# 3_3V_Converter.net
KiCad netlist of a schematic drawn in Altium Designer
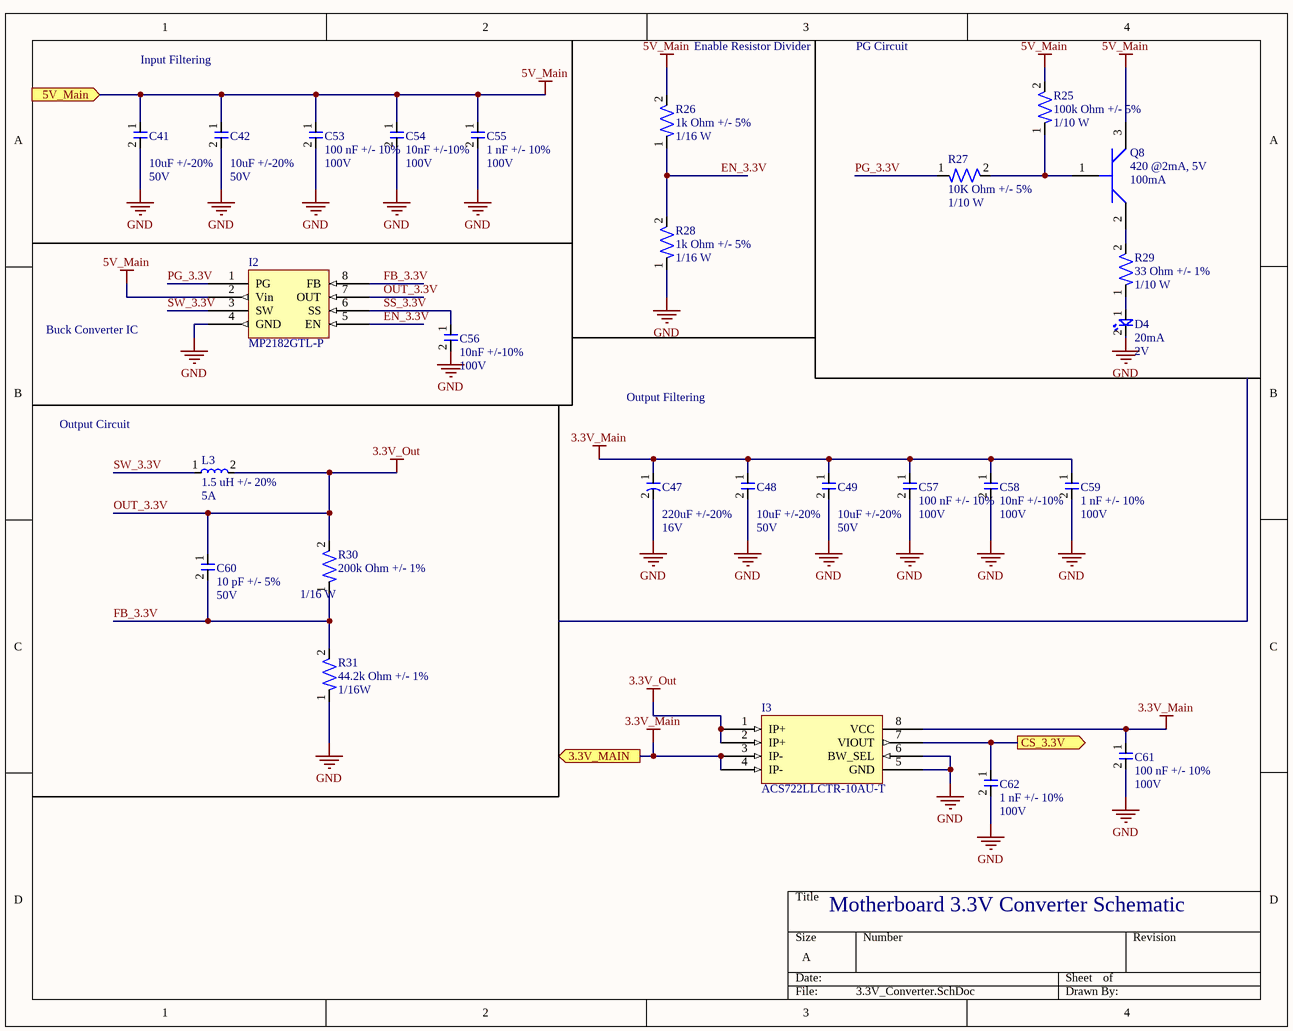
[diagram p0: 3.3V_Converter.SchDoc]

(export (version "E")
  (design (tool "Eeschema 10.0.6"))
  (components
    (comp (ref "C41")
      (value "CL31B106KBHNNNE")
      (footprint "CAP-1206")
      (description "10 µF ±10% 50V Ceramic Capacitor X7R 1206 (3216 Metric)")
      (fields
        (field (name "MANUFACTURER") "Samsung Electro-Mechanics")
        (field (name "CAPACITANCE") "10uF +/-20%")
        (field (name "VOLTAGE RATING") "50V")
      )
      (libsource (lib "MasterLib") (part "CAP-10U-0001"))
    )
    (comp (ref "C42")
      (value "CL31B106KBHNNNE")
      (footprint "CAP-1206")
      (description "10 µF ±10% 50V Ceramic Capacitor X7R 1206 (3216 Metric)")
      (fields
        (field (name "MANUFACTURER") "Samsung Electro-Mechanics")
        (field (name "CAPACITANCE") "10uF +/-20%")
        (field (name "VOLTAGE RATING") "50V")
      )
      (libsource (lib "MasterLib") (part "CAP-10U-0001"))
    )
    (comp (ref "C47")
      (value "UUD1C221MCL1GS")
      (footprint "ELEC-220U-0001")
      (description "220 µF 16 V Aluminum Electrolytic Capacitors Radial, Can - SMD 2000 Hrs @ 105°C")
      (fields
        (field (name "MANUFACTURER") "Nichicon")
        (field (name "CAPACITANCE") "220uF +/-20%")
        (field (name "VOLTAGE RATING") "16V")
      )
      (libsource (lib "MasterLib") (part "ELEC-220U-0001"))
    )
    (comp (ref "C48")
      (value "CL31B106KBHNNNE")
      (footprint "CAP-1206")
      (description "10 µF ±10% 50V Ceramic Capacitor X7R 1206 (3216 Metric)")
      (fields
        (field (name "MANUFACTURER") "Samsung Electro-Mechanics")
        (field (name "CAPACITANCE") "10uF +/-20%")
        (field (name "VOLTAGE RATING") "50V")
      )
      (libsource (lib "MasterLib") (part "CAP-10U-0001"))
    )
    (comp (ref "C49")
      (value "CL31B106KBHNNNE")
      (footprint "CAP-1206")
      (description "10 µF ±10% 50V Ceramic Capacitor X7R 1206 (3216 Metric)")
      (fields
        (field (name "MANUFACTURER") "Samsung Electro-Mechanics")
        (field (name "CAPACITANCE") "10uF +/-20%")
        (field (name "VOLTAGE RATING") "50V")
      )
      (libsource (lib "MasterLib") (part "CAP-10U-0001"))
    )
    (comp (ref "C53")
      (value "CC0603KRX7R0BB104")
      (footprint "CAP-0603")
      (description "100V 100nF X7R ±10% 0603 Multilayer Ceramic Capacitors MLCC - SMD/SMT ROHS")
      (fields
        (field (name "JLC PART NUMBER") "C113803")
        (field (name "CAPACITANCE") "100 nF +/- 10%")
        (field (name "VOLTAGE") "100V")
      )
      (libsource (lib "MasterLib") (part "CAP-100N-0002-JLC"))
    )
    (comp (ref "C54")
      (value "CC0603KRX7R0BB103")
      (footprint "CAP-0603")
      (description "100V 10nF X7R ±10% 0603 Multilayer Ceramic Capacitors MLCC - SMD/SMT ROHS")
      (fields
        (field (name "MANUFACTURER") "Yageo")
        (field (name "JLC PART NUMBER") "C107059")
        (field (name "CAPACITANCE") "10nF +/-10%")
        (field (name "VOLTAGE RATING") "100V")
      )
      (libsource (lib "MasterLib") (part "CAP-10N-0003-JLC"))
    )
    (comp (ref "C55")
      (value "C0402C102K1GECAUTO")
      (footprint "CAP-0402")
      (description "100V 1nF C0G ±10% 0402 Multilayer Ceramic Capacitors MLCC - SMD/SMT ROHS")
      (fields
        (field (name "CAPACITANCE") "1 nF +/- 10%")
        (field (name "VOLTAGE") "100V")
        (field (name "JLC PART NUMBER") "C696348")
      )
      (libsource (lib "MasterLib") (part "CAP-1N-0004-JLC"))
    )
    (comp (ref "C56")
      (value "CC0603KRX7R0BB103")
      (footprint "CAP-0603")
      (description "100V 10nF X7R ±10% 0603 Multilayer Ceramic Capacitors MLCC - SMD/SMT ROHS")
      (fields
        (field (name "MANUFACTURER") "Yageo")
        (field (name "JLC PART NUMBER") "C107059")
        (field (name "CAPACITANCE") "10nF +/-10%")
        (field (name "VOLTAGE RATING") "100V")
      )
      (libsource (lib "MasterLib") (part "CAP-10N-0003-JLC"))
    )
    (comp (ref "C57")
      (value "CC0603KRX7R0BB104")
      (footprint "CAP-0603")
      (description "100V 100nF X7R ±10% 0603 Multilayer Ceramic Capacitors MLCC - SMD/SMT ROHS")
      (fields
        (field (name "JLC PART NUMBER") "C113803")
        (field (name "CAPACITANCE") "100 nF +/- 10%")
        (field (name "VOLTAGE") "100V")
      )
      (libsource (lib "MasterLib") (part "CAP-100N-0002-JLC"))
    )
    (comp (ref "C58")
      (value "CC0603KRX7R0BB103")
      (footprint "CAP-0603")
      (description "100V 10nF X7R ±10% 0603 Multilayer Ceramic Capacitors MLCC - SMD/SMT ROHS")
      (fields
        (field (name "MANUFACTURER") "Yageo")
        (field (name "JLC PART NUMBER") "C107059")
        (field (name "CAPACITANCE") "10nF +/-10%")
        (field (name "VOLTAGE RATING") "100V")
      )
      (libsource (lib "MasterLib") (part "CAP-10N-0003-JLC"))
    )
    (comp (ref "C59")
      (value "C0402C102K1GECAUTO")
      (footprint "CAP-0402")
      (description "100V 1nF C0G ±10% 0402 Multilayer Ceramic Capacitors MLCC - SMD/SMT ROHS")
      (fields
        (field (name "CAPACITANCE") "1 nF +/- 10%")
        (field (name "VOLTAGE") "100V")
        (field (name "JLC PART NUMBER") "C696348")
      )
      (libsource (lib "MasterLib") (part "CAP-1N-0004-JLC"))
    )
    (comp (ref "C60")
      (value "CC0402JRNPO9BN100")
      (footprint "CAP-0402")
      (description "50V 10pF NP0 ±5% 0402 Multilayer Ceramic Capacitors MLCC - SMD/SMT ROHS")
      (fields
        (field (name "MANUFACTURER") "Yageo")
        (field (name "JLC PART NUMBER") "C106199")
        (field (name "CAPACITANCE") "10 pF +/- 5%")
        (field (name "VOLTAGE RATING") "50V")
      )
      (libsource (lib "MasterLib") (part "CAP-10P-0002-JLC"))
    )
    (comp (ref "C61")
      (value "CC0603KRX7R0BB104")
      (footprint "CAP-0603")
      (description "100V 100nF X7R ±10% 0603 Multilayer Ceramic Capacitors MLCC - SMD/SMT ROHS")
      (fields
        (field (name "JLC PART NUMBER") "C113803")
        (field (name "CAPACITANCE") "100 nF +/- 10%")
        (field (name "VOLTAGE") "100V")
      )
      (libsource (lib "MasterLib") (part "CAP-100N-0002-JLC"))
    )
    (comp (ref "C62")
      (value "C0402C102K1GECAUTO")
      (footprint "CAP-0402")
      (description "100V 1nF C0G ±10% 0402 Multilayer Ceramic Capacitors MLCC - SMD/SMT ROHS")
      (fields
        (field (name "CAPACITANCE") "1 nF +/- 10%")
        (field (name "VOLTAGE") "100V")
        (field (name "JLC PART NUMBER") "C696348")
      )
      (libsource (lib "MasterLib") (part "CAP-1N-0004-JLC"))
    )
    (comp (ref "D4")
      (value "150060AS75000")
      (footprint "LED-0603")
      (description "CAP CER 0.1UF 100V X7R 0603")
      (fields
        (field (name "MANUFACTURER") "Wurth Electronik")
        (field (name "CURRENT RATING") "20mA")
        (field (name "VF") "2V")
      )
      (libsource (lib "MasterLib") (part "LED_Amber_0001"))
    )
    (comp (ref "I2")
      (value "MP2182GTL-P")
      (footprint "IC-SOT583")
      (description "Buck Switching Regulator IC Positive Adjustable 0.6V 1 Output 2A SOT-583")
      (fields (field (name "MANUFACTURER") "Monolithic Power Systems"))
      (libsource (lib "MasterLib") (part "IC-BUCK-0003"))
    )
    (comp (ref "I3")
      (value "ACS722LLCTR-10AU-T")
      (footprint "IC-CURRENT-0001")
      (description "Current Sensor 10A 1 Channel Hall Effect, Open Loop Unidirectional 8-SOIC (0.154\", 3.90mm Width)")
      (libsource (lib "MasterLib") (part "IC-CURRENT-0001"))
    )
    (comp (ref "L3")
      (value "SRP3212-1R5M")
      (footprint "IND-1210")
      (description "1.5 µH Shielded Drum Core, Wirewound Inductor 4.4 A 53mOhm Max 1210 (3225 Metric)")
      (fields
        (field (name "MANUFACTURER") "Bourns Inc.")
        (field (name "INDUCTANCE") "1.5 uH +/- 20%")
        (field (name "SATURATION CURRENT") "5A")
      )
      (libsource (lib "MasterLib") (part "PWRIND-1.5U-0001"))
    )
    (comp (ref "Q8")
      (value "BC847C,235")
      (footprint "NPN-420-0001")
      (description "Bipolar (BJT) Transistor NPN 45 V 100 mA 100MHz 250 mW Surface Mount TO-236AB")
      (fields (field (name "HFE") "420 @2mA, 5V") (field (name "IC") "100mA"))
      (libsource (lib "MasterLib") (part "BJT-420-0001"))
    )
    (comp (ref "R25")
      (value "ERJ2GEJ104X")
      (footprint "RES-0402")
      (description "100mW Thick Film Resistors ±5% ±200ppm/℃ -55℃~+155℃ 100kΩ 0402  Chip Resistor - Surface Mount ROHS")
      (fields
        (field (name "RESISTANCE") "100k Ohm +/- 5%")
        (field (name "POWER") "1/10 W")
        (field (name "JLC PART NUMBER") "C413017")
      )
      (libsource (lib "MasterLib") (part "RES-100K-0002-JLC"))
    )
    (comp (ref "R26")
      (value "RC0402FR-071KL")
      (footprint "RES-0402")
      (fields
        (field (name "JLC PART NUMBER") "C106235")
        (field (name "RESISTANCE") "1k Ohm +/- 5%")
        (field (name "POWER") "1/16 W")
      )
      (libsource (lib "MasterLib") (part "RES-1K-0003-JLC"))
    )
    (comp (ref "R27")
      (value "ERJ2GEJ103X")
      (footprint "RES-0402")
      (fields
        (field (name "RESISTANCE") "10K Ohm +/- 5%")
        (field (name "POWER") "1/10 W")
        (field (name "JLC PART NUMBER") "C278577")
      )
      (libsource (lib "MasterLib") (part "RES-10K-0003-JLC"))
    )
    (comp (ref "R28")
      (value "RC0402FR-071KL")
      (footprint "RES-0402")
      (fields
        (field (name "JLC PART NUMBER") "C106235")
        (field (name "RESISTANCE") "1k Ohm +/- 5%")
        (field (name "POWER") "1/16 W")
      )
      (libsource (lib "MasterLib") (part "RES-1K-0003-JLC"))
    )
    (comp (ref "R29")
      (value "ERJ2RKF33R0X")
      (footprint "RES-0402")
      (description "100mW Thick Film Resistors ±100ppm/℃ ±1% -55℃~+155℃ 33Ω 0402  Chip Resistor - Surface Mount ROHS")
      (fields
        (field (name "RESISTANCE") "33 Ohm +/- 1%")
        (field (name "POWER") "1/10 W")
        (field (name "JLC PART NUMBER") "C278594")
      )
      (libsource (lib "MasterLib") (part "RES-33-0003-JLC"))
    )
    (comp (ref "R30")
      (value "RC-02W2003FT")
      (footprint "RES-0402")
      (description "62.5mW 50V ±1% ±200ppm/℃ -55℃~+155℃ 200kΩ 0402  Chip Resistor - Surface Mount ROHS")
      (fields
        (field (name "RESISTANCE") "200k Ohm +/- 1%")
        (field (name "JLC PART NUMBER") "C258094")
        (field (name "POWER") "1/16 W")
      )
      (libsource (lib "MasterLib") (part "RES-200K-0002-JLC"))
    )
    (comp (ref "R31")
      (value "RC0402FR-0744K2L")
      (footprint "RES-0402")
      (fields
        (field (name "RESISTANCE") "44.2k Ohm +/- 1%")
        (field (name "POWER") "1/16W")
        (field (name "JLC PART NUMBER") "C354260")
      )
      (libsource (lib "MasterLib") (part "RES-44.2K-0002-JLC"))
    )
  )
  (nets
    (net (code "1") (name "/CS_3.3V") (class "Default")
      (node (ref "C62") (pin "1") (pinfunction "1_1") (pintype "passive"))
      (node (ref "I3") (pin "7") (pinfunction "VIOUT_7") (pintype "output"))
    )
    (net (code "2") (name "/EN_3.3V") (class "Default")
      (node (ref "I2") (pin "5") (pinfunction "EN_5") (pintype "input"))
      (node (ref "R26") (pin "1") (pinfunction "1_1") (pintype "passive"))
      (node (ref "R28") (pin "2") (pinfunction "2_2") (pintype "passive"))
    )
    (net (code "3") (name "/FB_3.3V") (class "Default")
      (node (ref "C60") (pin "2") (pinfunction "2_2") (pintype "passive"))
      (node (ref "I2") (pin "8") (pinfunction "FB_8") (pintype "input"))
      (node (ref "R30") (pin "1") (pinfunction "1_1") (pintype "passive"))
      (node (ref "R31") (pin "2") (pinfunction "2_2") (pintype "passive"))
    )
    (net (code "4") (name "/PG_3.3V") (class "Default")
      (node (ref "I2") (pin "1") (pinfunction "PG_1") (pintype "power_in"))
      (node (ref "R27") (pin "1") (pinfunction "1_1") (pintype "passive"))
    )
    (net (code "5") (name "/SS_3.3V") (class "Default")
      (node (ref "C56") (pin "1") (pinfunction "1_1") (pintype "passive"))
      (node (ref "I2") (pin "6") (pinfunction "SS_6") (pintype "input"))
    )
    (net (code "6") (name "/SW_3.3V") (class "Default")
      (node (ref "I2") (pin "3") (pinfunction "SW_3") (pintype "power_in"))
      (node (ref "L3") (pin "1") (pinfunction "1_1") (pintype "passive"))
    )
    (net (code "7") (name "3.3V_Main") (class "Default")
      (node (ref "C47") (pin "1") (pinfunction "1_1") (pintype "passive"))
      (node (ref "C48") (pin "1") (pinfunction "1_1") (pintype "passive"))
      (node (ref "C49") (pin "1") (pinfunction "1_1") (pintype "passive"))
      (node (ref "C57") (pin "1") (pinfunction "1_1") (pintype "passive"))
      (node (ref "C58") (pin "1") (pinfunction "1_1") (pintype "passive"))
      (node (ref "C59") (pin "1") (pinfunction "1_1") (pintype "passive"))
      (node (ref "C61") (pin "1") (pinfunction "1_1") (pintype "passive"))
      (node (ref "I3") (pin "3") (pinfunction "IP-_3") (pintype "input"))
      (node (ref "I3") (pin "4") (pinfunction "IP-_4") (pintype "input"))
      (node (ref "I3") (pin "8") (pinfunction "VCC_8") (pintype "power_in"))
    )
    (net (code "8") (name "3.3V_Out") (class "Default")
      (node (ref "C60") (pin "1") (pinfunction "1_1") (pintype "passive"))
      (node (ref "I2") (pin "7") (pinfunction "OUT_7") (pintype "input"))
      (node (ref "I3") (pin "1") (pinfunction "IP+_1") (pintype "input"))
      (node (ref "I3") (pin "2") (pinfunction "IP+_2") (pintype "input"))
      (node (ref "L3") (pin "2") (pinfunction "2_2") (pintype "passive"))
      (node (ref "R30") (pin "2") (pinfunction "2_2") (pintype "passive"))
    )
    (net (code "9") (name "5V_Main") (class "Default")
      (node (ref "C41") (pin "1") (pinfunction "1_1") (pintype "passive"))
      (node (ref "C42") (pin "1") (pinfunction "1_1") (pintype "passive"))
      (node (ref "C53") (pin "1") (pinfunction "1_1") (pintype "passive"))
      (node (ref "C54") (pin "1") (pinfunction "1_1") (pintype "passive"))
      (node (ref "C55") (pin "1") (pinfunction "1_1") (pintype "passive"))
      (node (ref "I2") (pin "2") (pinfunction "Vin_2") (pintype "output"))
      (node (ref "Q8") (pin "3") (pintype "passive"))
      (node (ref "R25") (pin "2") (pinfunction "2_2") (pintype "passive"))
      (node (ref "R26") (pin "2") (pinfunction "2_2") (pintype "passive"))
    )
    (net (code "10") (name "GND") (class "Default")
      (node (ref "C41") (pin "2") (pinfunction "2_2") (pintype "passive"))
      (node (ref "C42") (pin "2") (pinfunction "2_2") (pintype "passive"))
      (node (ref "C47") (pin "2") (pinfunction "2_2") (pintype "passive"))
      (node (ref "C48") (pin "2") (pinfunction "2_2") (pintype "passive"))
      (node (ref "C49") (pin "2") (pinfunction "2_2") (pintype "passive"))
      (node (ref "C53") (pin "2") (pinfunction "2_2") (pintype "passive"))
      (node (ref "C54") (pin "2") (pinfunction "2_2") (pintype "passive"))
      (node (ref "C55") (pin "2") (pinfunction "2_2") (pintype "passive"))
      (node (ref "C56") (pin "2") (pinfunction "2_2") (pintype "passive"))
      (node (ref "C57") (pin "2") (pinfunction "2_2") (pintype "passive"))
      (node (ref "C58") (pin "2") (pinfunction "2_2") (pintype "passive"))
      (node (ref "C59") (pin "2") (pinfunction "2_2") (pintype "passive"))
      (node (ref "C61") (pin "2") (pinfunction "2_2") (pintype "passive"))
      (node (ref "C62") (pin "2") (pinfunction "2_2") (pintype "passive"))
      (node (ref "D4") (pin "2") (pinfunction "2_2") (pintype "passive"))
      (node (ref "I2") (pin "4") (pinfunction "GND_4") (pintype "output"))
      (node (ref "I3") (pin "5") (pinfunction "GND_5") (pintype "power_in"))
      (node (ref "I3") (pin "6") (pinfunction "BW_SEL_6") (pintype "input"))
      (node (ref "R28") (pin "1") (pinfunction "1_1") (pintype "passive"))
      (node (ref "R31") (pin "1") (pinfunction "1_1") (pintype "passive"))
    )
    (net (code "11") (name "Net-(D4-Pad1)") (class "Default")
      (node (ref "D4") (pin "1") (pinfunction "1_1") (pintype "passive"))
      (node (ref "R29") (pin "1") (pinfunction "1_1") (pintype "passive"))
    )
    (net (code "12") (name "Net-(Q8-Pad1)") (class "Default")
      (node (ref "Q8") (pin "1") (pinfunction "1_1") (pintype "passive"))
      (node (ref "R25") (pin "1") (pinfunction "1_1") (pintype "passive"))
      (node (ref "R27") (pin "2") (pinfunction "2_2") (pintype "passive"))
    )
    (net (code "13") (name "Net-(Q8-Pad2)") (class "Default")
      (node (ref "Q8") (pin "2") (pinfunction "2_2") (pintype "passive"))
      (node (ref "R29") (pin "2") (pinfunction "2_2") (pintype "passive"))
    )
  )
)
